# Digital_Pressure_Sensor.net
KiCad netlist of a schematic drawn in EAGLE
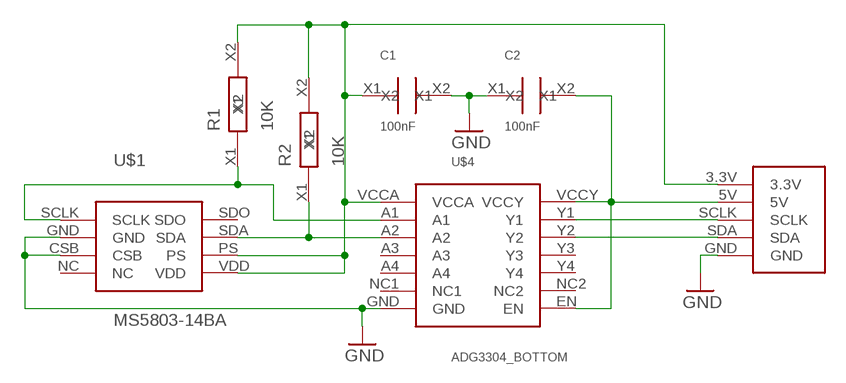
[diagram p0: schematic, sheet 1]

(export (version "E")
  (design (tool "Eeschema 10.0.6"))
  (components
    (comp (ref "C1")
      (value "100nF")
      (footprint "eagle-import:SMD_2.1X1.25_BOTTOM")
      (libsource (lib "eagle-import") (part "C_SMD_2.1X1.25_BOTTOM"))
    )
    (comp (ref "C2")
      (value "100nF")
      (footprint "eagle-import:SMD_2.1X1.25_BOTTOM")
      (libsource (lib "eagle-import") (part "C_SMD_2.1X1.25_BOTTOM"))
    )
    (comp (ref "R1")
      (value "10K")
      (footprint "eagle-import:SMD_2.1X1.25_BOTTOM")
      (libsource (lib "eagle-import") (part "R_SMD_2.1X1.25_BOTTOM"))
    )
    (comp (ref "R2")
      (value "10K")
      (footprint "eagle-import:SMD_2.1X1.25_BOTTOM")
      (libsource (lib "eagle-import") (part "R_SMD_2.1X1.25_BOTTOM"))
    )
    (comp (ref "U$1")
      (value "MS5803-14BA")
      (footprint "eagle-import:MS5803-14BA")
      (libsource (lib "eagle-import") (part "MS5803-14BA"))
    )
    (comp (ref "U$3")
      (value "5-PIN-PLUG")
      (footprint "eagle-import:5-PIN-PLUG")
      (libsource (lib "eagle-import") (part "5-PIN-PLUG"))
    )
    (comp (ref "U$4")
      (value "ADG3304_BOTTOM")
      (footprint "eagle-import:ADG3304_BOTTOM")
      (libsource (lib "eagle-import") (part "ADG3304_BOTTOM"))
    )
  )
  (nets
    (net (code "1") (name "GND") (class "Default")
      (node (ref "C1") (pin "X2") (pinfunction "X2_X2") (pintype "bidirectional"))
      (node (ref "C2") (pin "X1") (pinfunction "X1_X1") (pintype "bidirectional"))
      (node (ref "U$1") (pin "CSB") (pinfunction "CSB_CSB") (pintype "bidirectional"))
      (node (ref "U$1") (pin "GND") (pinfunction "GND_GND") (pintype "bidirectional"))
      (node (ref "U$3") (pin "GND") (pinfunction "GND_GND") (pintype "bidirectional"))
      (node (ref "U$4") (pin "GND") (pinfunction "GND_GND") (pintype "bidirectional"))
    )
    (net (code "2") (name "Net-(C1-PadX1)") (class "Default")
      (node (ref "C1") (pin "X1") (pinfunction "X1_X1") (pintype "bidirectional"))
      (node (ref "R1") (pin "X2") (pinfunction "X2_X2") (pintype "bidirectional"))
      (node (ref "R2") (pin "X2") (pinfunction "X2_X2") (pintype "bidirectional"))
      (node (ref "U$1") (pin "PS") (pinfunction "PS_PS") (pintype "bidirectional"))
      (node (ref "U$1") (pin "VDD") (pinfunction "VDD_VDD") (pintype "bidirectional"))
      (node (ref "U$3") (pin "3.3V") (pinfunction "3.3V_3.3V") (pintype "bidirectional"))
      (node (ref "U$4") (pin "VCCA") (pinfunction "VCCA_VCCA") (pintype "bidirectional"))
    )
    (net (code "3") (name "Net-(C2-PadX2)") (class "Default")
      (node (ref "C2") (pin "X2") (pinfunction "X2_X2") (pintype "bidirectional"))
      (node (ref "U$3") (pin "5V") (pinfunction "5V_5V") (pintype "bidirectional"))
      (node (ref "U$4") (pin "EN") (pinfunction "EN_EN") (pintype "bidirectional"))
      (node (ref "U$4") (pin "VCCY") (pinfunction "VCCY_VCCY") (pintype "bidirectional"))
    )
    (net (code "4") (name "Net-(R1-PadX1)") (class "Default")
      (node (ref "R1") (pin "X1") (pinfunction "X1_X1") (pintype "bidirectional"))
      (node (ref "U$1") (pin "SCLK") (pinfunction "SCLK_SCLK") (pintype "bidirectional"))
      (node (ref "U$4") (pin "A1") (pinfunction "A1_A1") (pintype "bidirectional"))
    )
    (net (code "5") (name "Net-(R2-PadX1)") (class "Default")
      (node (ref "R2") (pin "X1") (pinfunction "X1_X1") (pintype "bidirectional"))
      (node (ref "U$1") (pin "SDA") (pinfunction "SDA_SDA") (pintype "bidirectional"))
      (node (ref "U$4") (pin "A2") (pinfunction "A2_A2") (pintype "bidirectional"))
    )
    (net (code "6") (name "Net-(U$3-PadSCLK)") (class "Default")
      (node (ref "U$3") (pin "SCLK") (pinfunction "SCLK_SCLK") (pintype "bidirectional"))
      (node (ref "U$4") (pin "Y1") (pinfunction "Y1_Y1") (pintype "bidirectional"))
    )
    (net (code "7") (name "Net-(U$3-PadSDA)") (class "Default")
      (node (ref "U$3") (pin "SDA") (pinfunction "SDA_SDA") (pintype "bidirectional"))
      (node (ref "U$4") (pin "Y2") (pinfunction "Y2_Y2") (pintype "bidirectional"))
    )
    (net (code "8") (name "unconnected-(U$1-PadNC)") (class "Default")
      (node (ref "U$1") (pin "NC") (pinfunction "NC_NC") (pintype "bidirectional"))
    )
    (net (code "9") (name "unconnected-(U$1-PadSDO)") (class "Default")
      (node (ref "U$1") (pin "SDO") (pinfunction "SDO_SDO") (pintype "bidirectional"))
    )
    (net (code "10") (name "unconnected-(U$4-PadA3)") (class "Default")
      (node (ref "U$4") (pin "A3") (pinfunction "A3_A3") (pintype "bidirectional"))
    )
    (net (code "11") (name "unconnected-(U$4-PadA4)") (class "Default")
      (node (ref "U$4") (pin "A4") (pinfunction "A4_A4") (pintype "bidirectional"))
    )
    (net (code "12") (name "unconnected-(U$4-PadNC1)") (class "Default")
      (node (ref "U$4") (pin "NC1") (pinfunction "NC1_NC1") (pintype "bidirectional"))
    )
    (net (code "13") (name "unconnected-(U$4-PadNC2)") (class "Default")
      (node (ref "U$4") (pin "NC2") (pinfunction "NC2_NC2") (pintype "bidirectional"))
    )
    (net (code "14") (name "unconnected-(U$4-PadY3)") (class "Default")
      (node (ref "U$4") (pin "Y3") (pinfunction "Y3_Y3") (pintype "bidirectional"))
    )
    (net (code "15") (name "unconnected-(U$4-PadY4)") (class "Default")
      (node (ref "U$4") (pin "Y4") (pinfunction "Y4_Y4") (pintype "bidirectional"))
    )
  )
)
